# EVK-NORA-W4_SCHEM_0001_Power.net
KiCad netlist of a schematic drawn in Altium Designer
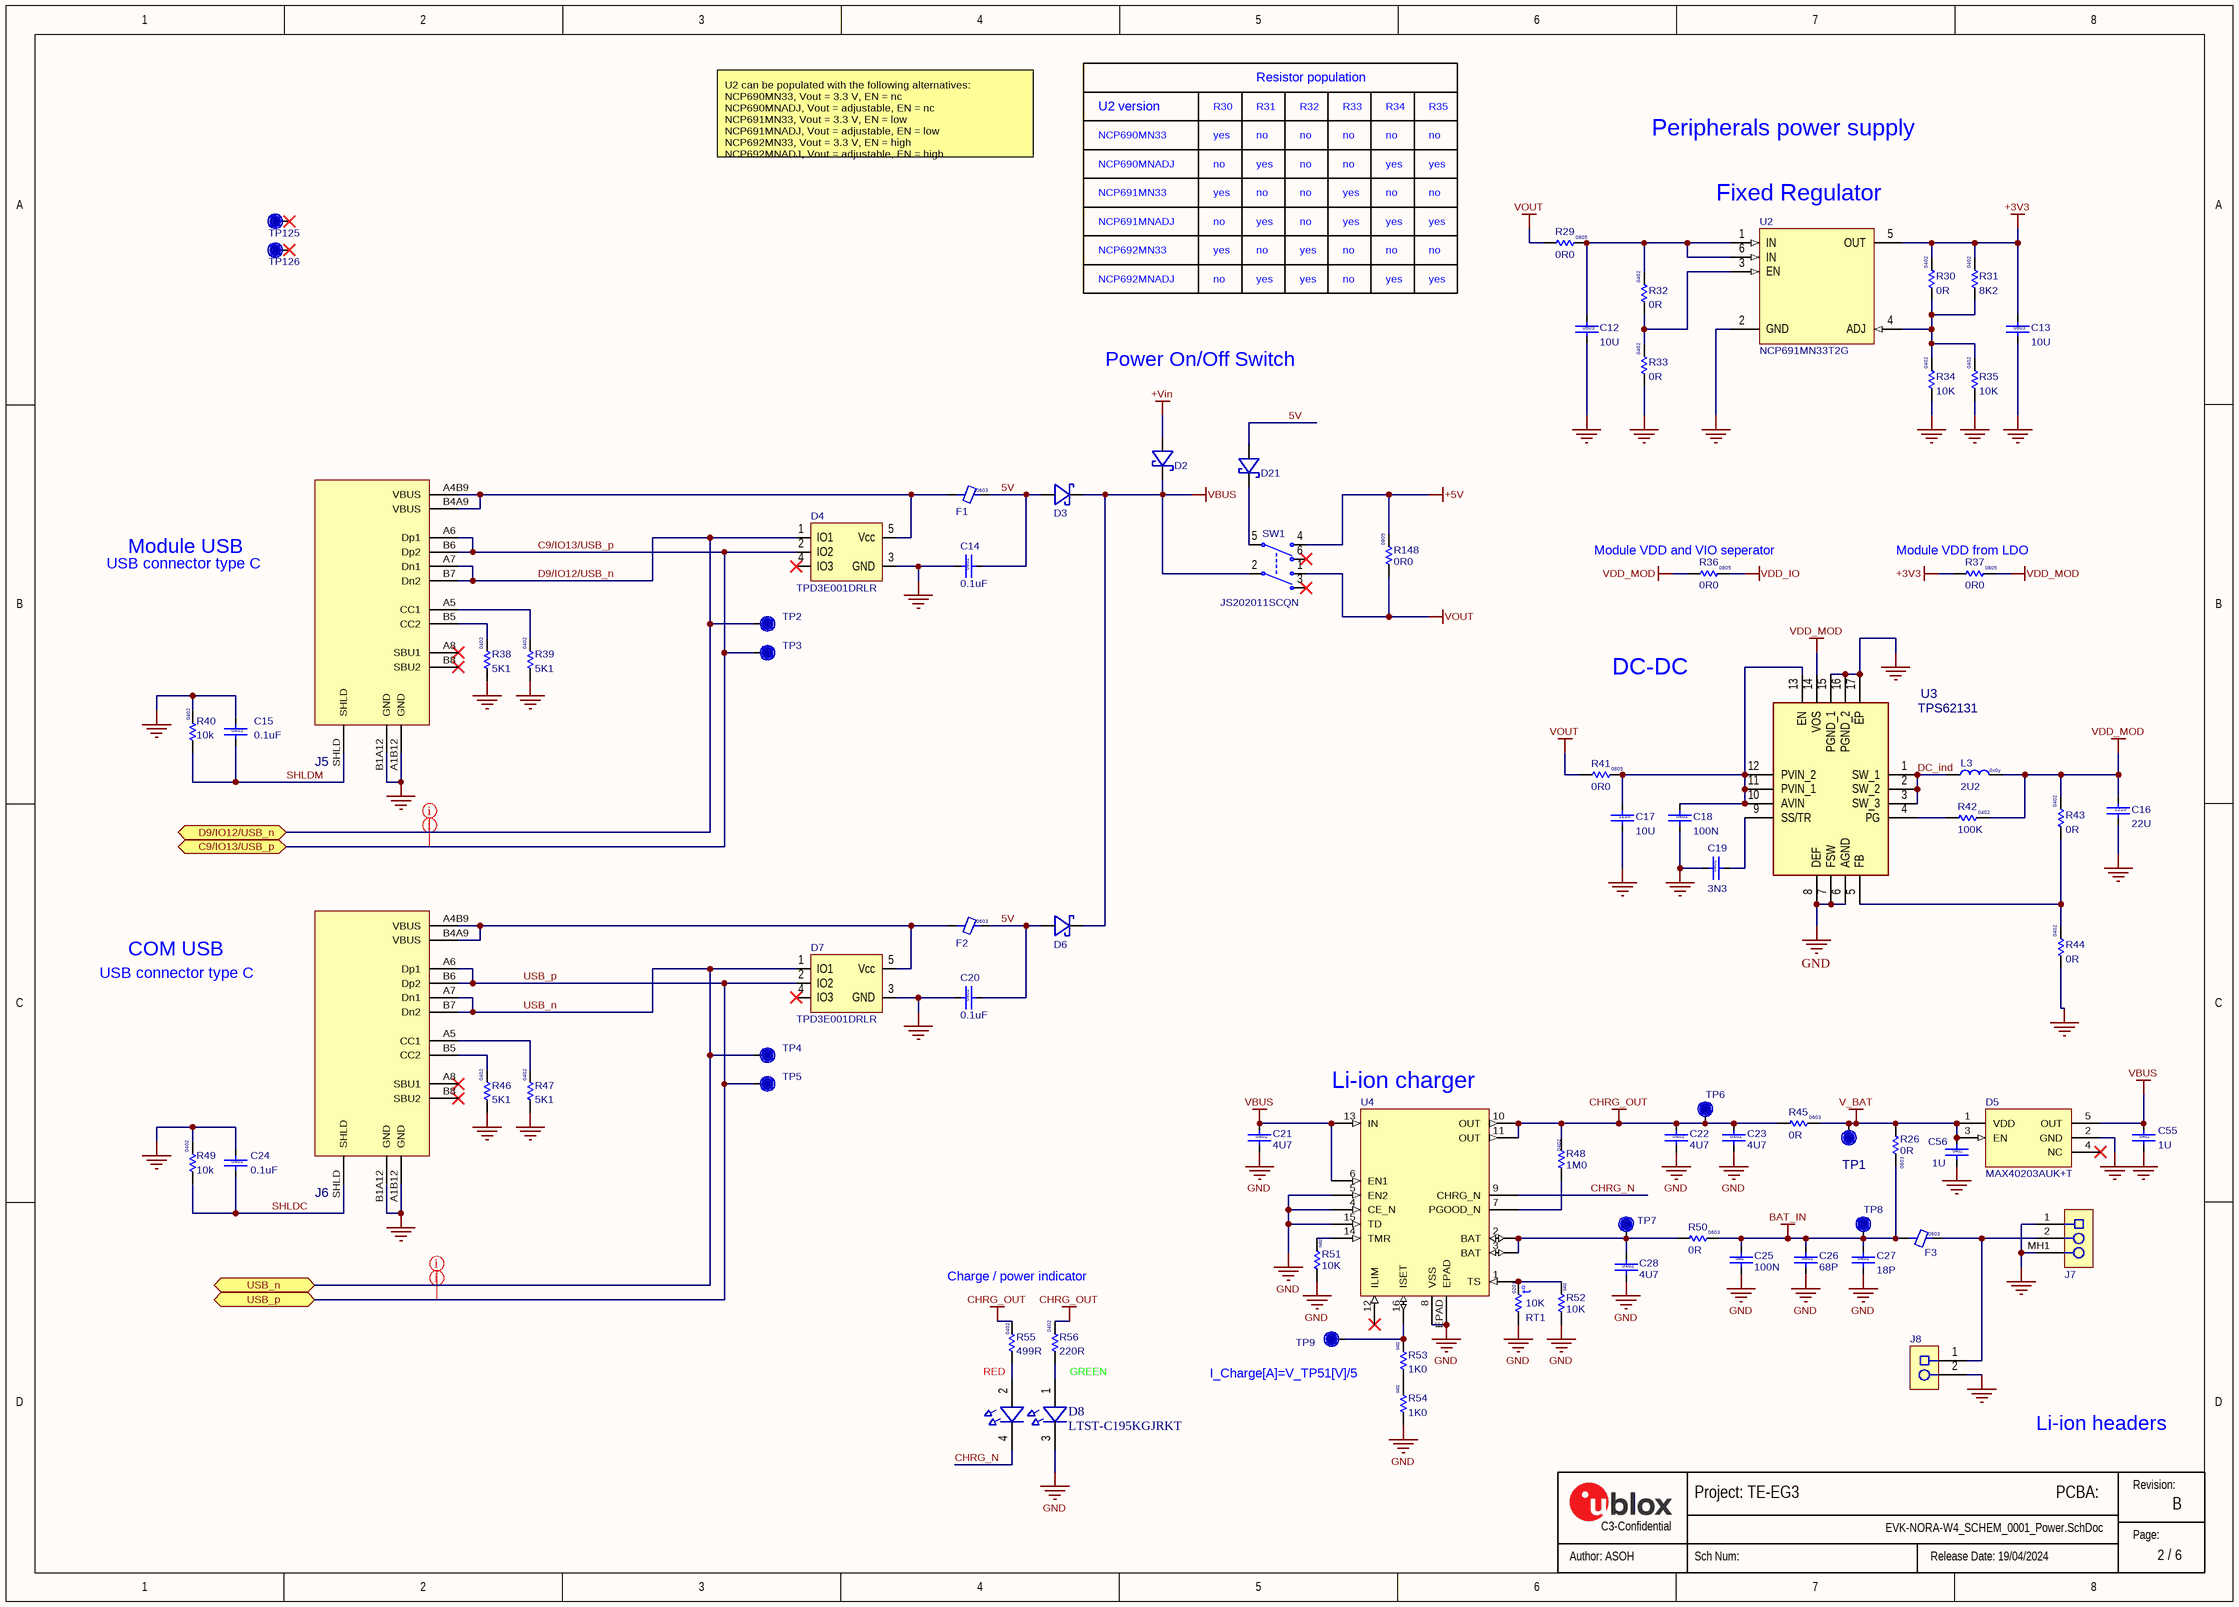
[diagram p0: EVK-NORA-W4_SCHEM_0001_Power.SchDoc]

(export (version "E")
  (design (tool "Eeschema 10.0.6"))
  (components
    (comp (ref "C12")
      (value "10U")
      (footprint "CAP_0603_1750Lx950Wx850H_600x1000Pad_900G_FLX")
      (description "CAP CER X7R 0603 10U 20% 10V")
      (fields
        (field (name "SIZE") "0603")
        (field (name "PART NUMBER") "UBXH01-0000310")
        (field (name "TOLERANCE") "20%")
        (field (name "EDITOR") "michael.hein")
        (field (name "RELEASED BY") "martin.grasse")
      )
      (libsource (lib "UBX_Parts_DB_Lib") (part "Cap Chip"))
    )
    (comp (ref "C13")
      (value "10U")
      (footprint "CAP_0603_1750Lx950Wx850H_600x1000Pad_900G_FLX")
      (description "CAP CER X7R 0603 10U 20% 10V")
      (fields
        (field (name "SIZE") "0603")
        (field (name "PART NUMBER") "UBXH01-0000310")
        (field (name "TOLERANCE") "20%")
        (field (name "EDITOR") "michael.hein")
        (field (name "RELEASED BY") "martin.grasse")
      )
      (libsource (lib "UBX_Parts_DB_Lib") (part "Cap Chip"))
    )
    (comp (ref "C14")
      (value "0.1uF")
      (footprint "Cap 0402 HD")
      (description "Cap, Ceramic 0.1uF 10V 10% X5R 0402")
      (fields
        (field (name "SIZE") "0402")
        (field (name "PART NUMBER") "120-00016")
        (field (name "MANUFACTURER") "Murata Electronics North America")
      )
      (libsource (lib "Arena_Parts_DB_Lib") (part "Cap Chip"))
    )
    (comp (ref "C15")
      (value "0.1uF")
      (footprint "Cap 0402 HD")
      (description "Cap, Ceramic 0.1uF 10V 10% X5R 0402")
      (fields
        (field (name "SIZE") "0402")
        (field (name "PART NUMBER") "120-00016")
        (field (name "MANUFACTURER") "Murata Electronics North America")
      )
      (libsource (lib "Arena_Parts_DB_Lib") (part "Cap Chip"))
    )
    (comp (ref "C16")
      (value "22U")
      (footprint "CAP_1210_3400Lx2700Wx1350H_900x2700Pad_1900G_FLX")
      (description "CAP CER X5R 1210 22U 10% 25V")
      (fields
        (field (name "SIZE") "1210")
        (field (name "PART NUMBER") "UBXH01-3001005")
        (field (name "TOLERANCE") "10%")
        (field (name "EDITOR") "roland.rust")
        (field (name "RELEASED BY") "roland.rust")
      )
      (libsource (lib "UBX_Parts_DB_Lib") (part "Cap Chip"))
    )
    (comp (ref "C17")
      (value "10U")
      (footprint "CAP_1210_3400Lx2700Wx1350H_900x2700Pad_1900G_FLX")
      (description "CAP CER X5R 1210 10U 10% 25V")
      (fields
        (field (name "SIZE") "1210")
        (field (name "PART NUMBER") "UBXH01-3001004")
        (field (name "TOLERANCE") "10%")
        (field (name "EDITOR") "andreas.thiel")
        (field (name "RELEASED BY") "johann.furrer")
      )
      (libsource (lib "UBX_Parts_DB_Lib") (part "Cap Chip"))
    )
    (comp (ref "C18")
      (value "100N")
      (footprint "Cap_0402_1100Lx600Wx600H_600x600Pad_350G_FLX")
      (description "CAP CER X5R 0402 100N 10% 50V")
      (fields
        (field (name "SIZE") "0402")
        (field (name "PART NUMBER") "UBXH01-0000204")
        (field (name "TOLERANCE") "10%")
        (field (name "EDITOR") "matej.budin")
        (field (name "RELEASED BY") "erian.bezhani")
      )
      (libsource (lib "UBX_Parts_DB_Lib") (part "Cap Chip"))
    )
    (comp (ref "C19")
      (value "3N3")
      (footprint "Cap_0402_1100Lx600Wx600H_600x600Pad_350G_FLX")
      (description "CAP CER X7R 0402 3N3 10% 16V")
      (fields
        (field (name "SIZE") "0402")
        (field (name "PART NUMBER") "UBXH01-0023019")
        (field (name "TOLERANCE") "10%")
        (field (name "EDITOR") "dario.antonaz")
        (field (name "RELEASED BY") "pierpaolo.arban")
      )
      (libsource (lib "UBX_Parts_DB_Lib") (part "Cap Chip"))
    )
    (comp (ref "C20")
      (value "0.1uF")
      (footprint "Cap 0402 HD")
      (description "Cap, Ceramic 0.1uF 10V 10% X5R 0402")
      (fields
        (field (name "SIZE") "0402")
        (field (name "PART NUMBER") "120-00016")
        (field (name "MANUFACTURER") "Murata Electronics North America")
      )
      (libsource (lib "Arena_Parts_DB_Lib") (part "Cap Chip"))
    )
    (comp (ref "C21")
      (value "4U7")
      (footprint "Cap 0402 HD")
      (description "CAP CER X5R 0402 4U7 20% 10V")
      (fields
        (field (name "SIZE") "0402")
        (field (name "PART NUMBER") "UBXH01-0000243")
        (field (name "TOLERANCE") "20%")
        (field (name "EDITOR") "martin.pilik")
        (field (name "RELEASED BY") "fabrice.bret-dibat")
      )
      (libsource (lib "UBX_Parts_DB_Lib") (part "Cap Chip"))
    )
    (comp (ref "C22")
      (value "4U7")
      (footprint "Cap 0402 HD")
      (description "CAP CER X5R 0402 4U7 20% 10V")
      (fields
        (field (name "SIZE") "0402")
        (field (name "PART NUMBER") "UBXH01-0000243")
        (field (name "TOLERANCE") "20%")
        (field (name "EDITOR") "martin.pilik")
        (field (name "RELEASED BY") "fabrice.bret-dibat")
      )
      (libsource (lib "UBX_Parts_DB_Lib") (part "Cap Chip"))
    )
    (comp (ref "C23")
      (value "4U7")
      (footprint "Cap 0402 HD")
      (description "CAP CER X5R 0402 4U7 20% 10V")
      (fields
        (field (name "SIZE") "0402")
        (field (name "PART NUMBER") "UBXH01-0000243")
        (field (name "TOLERANCE") "20%")
        (field (name "EDITOR") "martin.pilik")
        (field (name "RELEASED BY") "fabrice.bret-dibat")
      )
      (libsource (lib "UBX_Parts_DB_Lib") (part "Cap Chip"))
    )
    (comp (ref "C24")
      (value "0.1uF")
      (footprint "Cap 0402 HD")
      (description "Cap, Ceramic 0.1uF 10V 10% X5R 0402")
      (fields
        (field (name "SIZE") "0402")
        (field (name "PART NUMBER") "120-00016")
        (field (name "MANUFACTURER") "Murata Electronics North America")
      )
      (libsource (lib "Arena_Parts_DB_Lib") (part "Cap Chip"))
    )
    (comp (ref "C25")
      (value "100N")
      (footprint "Cap 0402 HD")
      (description "CAP CER X5R 0402 100N 10% 10V")
      (fields
        (field (name "SIZE") "0402")
        (field (name "PART NUMBER") "UBXH01-2021002")
        (field (name "TOLERANCE") "10%")
        (field (name "EDITOR") "roland.rust")
        (field (name "RELEASED BY") "roland.rust")
      )
      (libsource (lib "UBX_Parts_DB_Lib") (part "Cap Chip"))
    )
    (comp (ref "C26")
      (value "68P")
      (footprint "Cap 0402 HD")
      (description "CAP CER C0G 0402 68P 5% 25V")
      (fields
        (field (name "SIZE") "0402")
        (field (name "PART NUMBER") "UBXH01-0004024")
        (field (name "TOLERANCE") "5%")
        (field (name "EDITOR") "martin.frauchiger")
        (field (name "RELEASED BY") "martin.frauchiger")
      )
      (libsource (lib "UBX_Parts_DB_Lib") (part "Cap Chip"))
    )
    (comp (ref "C27")
      (value "18P")
      (footprint "Cap_0402_1100Lx600Wx600H_600x600Pad_350G_FLX")
      (description "CAP CER C0G 0402 18P 5% 25V")
      (fields
        (field (name "SIZE") "0402")
        (field (name "PART NUMBER") "UBXH01-0004017")
        (field (name "TOLERANCE") "5%")
        (field (name "EDITOR") "doris.zahnd")
        (field (name "RELEASED BY") "daniel.hurni")
      )
      (libsource (lib "UBX_Parts_DB_Lib") (part "Cap Chip"))
    )
    (comp (ref "C28")
      (value "4U7")
      (footprint "Cap 0402 HD")
      (description "CAP CER X5R 0402 4U7 20% 10V")
      (fields
        (field (name "SIZE") "0402")
        (field (name "PART NUMBER") "UBXH01-0000243")
        (field (name "TOLERANCE") "20%")
        (field (name "EDITOR") "martin.pilik")
        (field (name "RELEASED BY") "fabrice.bret-dibat")
      )
      (libsource (lib "UBX_Parts_DB_Lib") (part "Cap Chip"))
    )
    (comp (ref "C55")
      (value "1U")
      (footprint "Cap 0402 HD")
      (description "CAP CER X5R 0402 1U 10% 10V")
      (fields
        (field (name "SIZE") "0402")
        (field (name "PART NUMBER") "UBXH01-0000248")
        (field (name "TOLERANCE") "10%")
        (field (name "EDITOR") "michael.hein")
        (field (name "RELEASED BY") "igor.shevchenko")
      )
      (libsource (lib "UBX_Parts_DB_Lib") (part "Cap Chip"))
    )
    (comp (ref "C56")
      (value "1U")
      (footprint "Cap 0402 HD")
      (description "CAP CER X5R 0402 1U 10% 10V")
      (fields
        (field (name "SIZE") "0402")
        (field (name "PART NUMBER") "UBXH01-0000248")
        (field (name "TOLERANCE") "10%")
        (field (name "EDITOR") "michael.hein")
        (field (name "RELEASED BY") "igor.shevchenko")
      )
      (libsource (lib "UBX_Parts_DB_Lib") (part "Cap Chip"))
    )
    (comp (ref "D2")
      (value "110-00005")
      (footprint "SOD-123F_U")
      (description "Diode, Schottky, 20V 1A SOD-123F, 340mV Vf @ 1A\nMBR120VLSFT3G")
      (fields (field (name "VOLTAGE") "20V"))
      (libsource (lib "Arena_Parts_DB_Lib") (part "Diode_Schottky"))
    )
    (comp (ref "D3")
      (value "110-00005")
      (footprint "SOD-123F_U")
      (description "Diode, Schottky, 20V 1A SOD-123F, 340mV Vf @ 1A\nMBR120VLSFT3G")
      (fields (field (name "VOLTAGE") "20V"))
      (libsource (lib "Arena_Parts_DB_Lib") (part "Diode_Schottky"))
    )
    (comp (ref "D4")
      (value "110-00018")
      (footprint "SOT-553")
      (description "LOW-CAPACITANCE 3-CHANNEL ESD-PROTECTION ARRAY")
      (fields
        (field (name "MANUFACTURER P/N") "TPD3E001DRLR")
        (field (name "MANUFACTURER") "Texas Instruments")
        (field (name "VOLTAGE") "5V")
      )
      (libsource (lib "Arena_Parts_DB_Lib") (part "TPD3E001"))
    )
    (comp (ref "D5")
      (value "UBXH12-0000539")
      (footprint "SOT-23-5_2")
      (description "IDEAL DIODE OR CONTROLLER SOURCE SELECTOR SWITCH P-CHANNEL 1:1 SOT-23-5 5.5V 1A")
      (fields
        (field (name "VOLTAGE") "5.5V")
        (field (name "MANUFACTURER PART NUMBER 1") "MAX40203AUK+T")
        (field (name "MANUFACTURER") "Maxim")
        (field (name "EDITOR") "eric.moog")
      )
      (libsource (lib "UBX_Parts_DB_Lib") (part "MAX40203AUK"))
    )
    (comp (ref "D6")
      (value "110-00005")
      (footprint "SOD-123F_U")
      (description "Diode, Schottky, 20V 1A SOD-123F, 340mV Vf @ 1A\nMBR120VLSFT3G")
      (fields (field (name "VOLTAGE") "20V"))
      (libsource (lib "Arena_Parts_DB_Lib") (part "Diode_Schottky"))
    )
    (comp (ref "D7")
      (value "110-00018")
      (footprint "SOT-553")
      (description "LOW-CAPACITANCE 3-CHANNEL ESD-PROTECTION ARRAY")
      (fields
        (field (name "MANUFACTURER P/N") "TPD3E001DRLR")
        (field (name "MANUFACTURER") "Texas Instruments")
        (field (name "VOLTAGE") "5V")
      )
      (libsource (lib "Arena_Parts_DB_Lib") (part "TPD3E001"))
    )
    (comp (ref "D8")
      (value "LTST-C195KGJRKT")
      (footprint "SamacSys:LTSTC195KGJRKT")
      (description "LED")
      (fields (field (name "MOUSER PART NUMBER") "859-LTST-C195KGJRKT"))
      (libsource (lib "SamacSys") (part "LTST-C195KGJRKT"))
    )
    (comp (ref "D21")
      (value "110-00005")
      (footprint "SOD-123F_U")
      (description "Diode, Schottky, 20V 1A SOD-123F, 340mV Vf @ 1A\nMBR120VLSFT3G")
      (fields (field (name "VOLTAGE") "20V"))
      (libsource (lib "Arena_Parts_DB_Lib") (part "Diode_Schottky"))
    )
    (comp (ref "F1")
      (value "UBXH08-0000001")
      (footprint "IND_0603_1750Lx950Wx1050H_600x800Pad_800G_FLX")
      (description "FERRITE BEAD 0603 600 OHM AT 100MHZ 600OHM 500mA")
      (fields
        (field (name "SIZE") "0603")
        (field (name "MANUFACTURER") "TDK Corporation")
        (field (name "EDITOR") "daniel.hurni")
        (field (name "RELEASED BY") "martin.frauchiger")
      )
      (libsource (lib "UBX_Parts_DB_Lib") (part "FB sm"))
    )
    (comp (ref "F2")
      (value "UBXH08-0000001")
      (footprint "IND_0603_1750Lx950Wx1050H_600x800Pad_800G_FLX")
      (description "FERRITE BEAD 0603 600 OHM AT 100MHZ 600OHM 500mA")
      (fields
        (field (name "SIZE") "0603")
        (field (name "MANUFACTURER") "TDK Corporation")
        (field (name "EDITOR") "daniel.hurni")
        (field (name "RELEASED BY") "martin.frauchiger")
      )
      (libsource (lib "UBX_Parts_DB_Lib") (part "FB sm"))
    )
    (comp (ref "F3")
      (value "UBXH08-0000001")
      (footprint "IND_0603_1750Lx950Wx1050H_600x800Pad_800G_FLX")
      (description "FERRITE BEAD 0603 600 OHM AT 100MHZ 600OHM 500mA")
      (fields
        (field (name "SIZE") "0603")
        (field (name "MANUFACTURER") "TDK Corporation")
        (field (name "EDITOR") "daniel.hurni")
        (field (name "RELEASED BY") "martin.frauchiger")
      )
      (libsource (lib "UBX_Parts_DB_Lib") (part "FB sm"))
    )
    (comp (ref "J5")
      (value "USB4105-GF-A")
      (footprint "USB4105-GF-A")
      (description "CONN RCP USB2.0 TYP C 24P SMD RA 20V 6.25A")
      (fields
        (field (name "PART NUMBER") "UBXH04-0000785")
        (field (name "VOLTAGE") "<20V DC")
        (field (name "EDITOR") "eric.moog")
      )
      (libsource (lib "UBX_Parts_DB_Lib") (part "USB4105-GF-A"))
    )
    (comp (ref "J6")
      (value "USB4105-GF-A")
      (footprint "USB4105-GF-A")
      (description "CONN RCP USB2.0 TYP C 24P SMD RA 20V 6.25A")
      (fields
        (field (name "PART NUMBER") "UBXH04-0000785")
        (field (name "VOLTAGE") "<20V DC")
        (field (name "EDITOR") "eric.moog")
      )
      (libsource (lib "UBX_Parts_DB_Lib") (part "USB4105-GF-A"))
    )
    (comp (ref "J7")
      (value "UBXH04-0000791")
      (footprint "B2B-PH-SM4-TB")
      (description "CONN 1-ROW SMT 2.0MM GRID 2-PIN VERT 100V 2A")
      (fields
        (field (name "VOLTAGE") "None")
        (field (name "MANUFACTURER") "JST")
        (field (name "EDITOR") "eric.moog")
      )
      (libsource (lib "UBX_Parts_DB_Lib") (part "CON-2Pin_1Row_W-MH"))
    )
    (comp (ref "J8")
      (value "UBXH04-0000026")
      (footprint "HDR-0.1P-2PIN-TH")
      (description "1-ROW TH-PCB SOCKETS 100MIL GRID 2-PIN 0.64MM SQUARE POLARIZE")
      (fields
        (field (name "MANUFACTURER") "HARWiN")
        (field (name "EDITOR") "roland.rust")
        (field (name "RELEASED BY") "alvaro.nussbaum")
      )
      (libsource (lib "UBX_Parts_DB_Lib") (part "CON-2Pin_1Row"))
    )
    (comp (ref "L3")
      (value "2U2")
      (footprint "IND_0603_1800Lx1000Wx1000H_600x1000Pad_650G_FLX")
      (description "IND TAIYOYUDEN MCHK1608T 2U2 20% 1.5A")
      (fields
        (field (name "SIZE") "0x0y")
        (field (name "PART NUMBER") "UBXH09-0000330")
        (field (name "TOLERANCE") "20%")
        (field (name "EDITOR") "martin.grasse")
        (field (name "RELEASED BY") "igor.shevchenko")
      )
      (libsource (lib "UBX_Parts_DB_Lib") (part "Ind sm"))
    )
    (comp (ref "R26")
      (value "0R")
      (footprint "RES_0603_1700Lx950Wx600H_600x1000Pad_800G_FLX")
      (description "RES THICK FILM CHIP 0603 0R 0 100mW")
      (fields
        (field (name "SIZE") "0603")
        (field (name "PART NUMBER") "UBXH18-0003001")
        (field (name "TOLERANCE") "0")
        (field (name "EDITOR") "martin.frauchiger")
        (field (name "RELEASED BY") "martin.frauchiger")
      )
      (libsource (lib "UBX_Parts_DB_Lib") (part "Res sm"))
    )
    (comp (ref "R29")
      (value "0R0")
      (footprint "RES 0805_2150Lx1400Wx650H_800x1300Pad_1000G_FLX")
      (description "RES THICK FILM CHIP 0805 0R015 1% 330mW")
      (fields
        (field (name "SIZE") "0805")
        (field (name "TOLERANCE") "1%")
        (field (name "MANUFACTURER") "KOA Speer Electronics, Inc.")
        (field (name "EDITOR") "roland.rust")
        (field (name "RELEASED BY") "frank.felbier")
      )
      (libsource (lib "UBX_Parts_DB_Lib") (part "Res sm"))
    )
    (comp (ref "R30")
      (value "0R")
      (footprint "RES 0402 HD")
      (description "RES THICK FILM CHIP 0402 0R 0 100mW")
      (fields
        (field (name "SIZE") "0402")
        (field (name "PART NUMBER") "UBXH18-0003002")
        (field (name "TOLERANCE") "0")
        (field (name "EDITOR") "charlotte.biber")
        (field (name "RELEASED BY") "peter.mueller")
      )
      (libsource (lib "UBX_Parts_DB_Lib") (part "Res sm"))
    )
    (comp (ref "R31")
      (value "8K2")
      (footprint "RES_0402_1100Lx600Wx400H_500x600Pad_400G_FLX")
      (description "RES THICK FILM CHIP 0402 8K2 1% 63mW")
      (fields
        (field (name "SIZE") "0402")
        (field (name "PART NUMBER") "UBXH18-0000138")
        (field (name "TOLERANCE") "1%")
        (field (name "EDITOR") "matej.budin")
        (field (name "RELEASED BY") "pasquale.scorca")
      )
      (libsource (lib "UBX_Parts_DB_Lib") (part "Res sm"))
    )
    (comp (ref "R32")
      (value "0R")
      (footprint "RES 0402 HD")
      (description "RES THICK FILM CHIP 0402 0R 0 100mW")
      (fields
        (field (name "SIZE") "0402")
        (field (name "PART NUMBER") "UBXH18-0003002")
        (field (name "TOLERANCE") "0")
        (field (name "EDITOR") "charlotte.biber")
        (field (name "RELEASED BY") "peter.mueller")
      )
      (libsource (lib "UBX_Parts_DB_Lib") (part "Res sm"))
    )
    (comp (ref "R33")
      (value "0R")
      (footprint "RES 0402 HD")
      (description "RES THICK FILM CHIP 0402 0R 0 100mW")
      (fields
        (field (name "SIZE") "0402")
        (field (name "PART NUMBER") "UBXH18-0003002")
        (field (name "TOLERANCE") "0")
        (field (name "EDITOR") "charlotte.biber")
        (field (name "RELEASED BY") "peter.mueller")
      )
      (libsource (lib "UBX_Parts_DB_Lib") (part "Res sm"))
    )
    (comp (ref "R34")
      (value "10K")
      (footprint "RES 0402 HD")
      (description "RES THICK FILM CHIP 0402 10K 1% 63mW")
      (fields
        (field (name "SIZE") "0402")
        (field (name "PART NUMBER") "UBXH18-0000065")
        (field (name "TOLERANCE") "1%")
        (field (name "EDITOR") "erian.bezhani")
        (field (name "RELEASED BY") "massimo.vlacci")
      )
      (libsource (lib "UBX_Parts_DB_Lib") (part "Res sm"))
    )
    (comp (ref "R35")
      (value "10K")
      (footprint "RES 0402 HD")
      (description "RES THICK FILM CHIP 0402 10K 1% 63mW")
      (fields
        (field (name "SIZE") "0402")
        (field (name "PART NUMBER") "UBXH18-0000065")
        (field (name "TOLERANCE") "1%")
        (field (name "EDITOR") "erian.bezhani")
        (field (name "RELEASED BY") "massimo.vlacci")
      )
      (libsource (lib "UBX_Parts_DB_Lib") (part "Res sm"))
    )
    (comp (ref "R36")
      (value "0R0")
      (footprint "RES 0805_2150Lx1400Wx650H_800x1300Pad_1000G_FLX")
      (description "RES THICK FILM CHIP 0805 0R015 1% 330mW")
      (fields
        (field (name "SIZE") "0805")
        (field (name "TOLERANCE") "1%")
        (field (name "MANUFACTURER") "KOA Speer Electronics, Inc.")
        (field (name "EDITOR") "roland.rust")
        (field (name "RELEASED BY") "frank.felbier")
      )
      (libsource (lib "UBX_Parts_DB_Lib") (part "Res sm"))
    )
    (comp (ref "R37")
      (value "0R0")
      (footprint "RES 0805_2150Lx1400Wx650H_800x1300Pad_1000G_FLX")
      (description "RES THICK FILM CHIP 0805 0R015 1% 330mW")
      (fields
        (field (name "SIZE") "0805")
        (field (name "TOLERANCE") "1%")
        (field (name "MANUFACTURER") "KOA Speer Electronics, Inc.")
        (field (name "EDITOR") "roland.rust")
        (field (name "RELEASED BY") "frank.felbier")
      )
      (libsource (lib "UBX_Parts_DB_Lib") (part "Res sm"))
    )
    (comp (ref "R38")
      (value "5K1")
      (footprint "RES 0402 HD")
      (description "RES THICK FILM CHIP 0402 5K1 5% 100mW")
      (fields
        (field (name "SIZE") "0402")
        (field (name "PART NUMBER") "UBXH18-0008066")
        (field (name "TOLERANCE") "5%")
        (field (name "EDITOR") "alvaro.nussbaum")
        (field (name "RELEASED BY") "roland.rust")
      )
      (libsource (lib "UBX_Parts_DB_Lib") (part "Res sm"))
    )
    (comp (ref "R39")
      (value "5K1")
      (footprint "RES 0402 HD")
      (description "RES THICK FILM CHIP 0402 5K1 5% 100mW")
      (fields
        (field (name "SIZE") "0402")
        (field (name "PART NUMBER") "UBXH18-0008066")
        (field (name "TOLERANCE") "5%")
        (field (name "EDITOR") "alvaro.nussbaum")
        (field (name "RELEASED BY") "roland.rust")
      )
      (libsource (lib "UBX_Parts_DB_Lib") (part "Res sm"))
    )
    (comp (ref "R40")
      (value "10k")
      (footprint "RES 0402 HD")
      (description "Resistor 10k ohm 1% 1/16W, 0402")
      (fields
        (field (name "SIZE") "0402")
        (field (name "PART NUMBER") "180-00024")
        (field (name "POWER") "1/16W")
      )
      (libsource (lib "Arena_Parts_DB_Lib") (part "Res sm"))
    )
    (comp (ref "R41")
      (value "0R0")
      (footprint "RES 0805_2150Lx1400Wx650H_800x1300Pad_1000G_FLX")
      (description "RES THICK FILM CHIP 0805 0R015 1% 330mW")
      (fields
        (field (name "SIZE") "0805")
        (field (name "TOLERANCE") "1%")
        (field (name "MANUFACTURER") "KOA Speer Electronics, Inc.")
        (field (name "EDITOR") "roland.rust")
        (field (name "RELEASED BY") "frank.felbier")
      )
      (libsource (lib "UBX_Parts_DB_Lib") (part "Res sm"))
    )
    (comp (ref "R42")
      (value "100K")
      (footprint "RES 0402 HD")
      (description "RES THICK FILM CHIP 0402 100K 1% 63mW")
      (fields
        (field (name "SIZE") "0402")
        (field (name "PART NUMBER") "UBXH18-0000005")
        (field (name "TOLERANCE") "1%")
        (field (name "EDITOR") "dario.antonaz")
        (field (name "RELEASED BY") "sandro.sestan")
      )
      (libsource (lib "UBX_Parts_DB_Lib") (part "Res sm"))
    )
    (comp (ref "R43")
      (value "0R")
      (footprint "RES 0402 HD")
      (description "RES THICK FILM CHIP 0402 0R 0 100mW")
      (fields
        (field (name "SIZE") "0402")
        (field (name "PART NUMBER") "UBXH18-0003002")
        (field (name "TOLERANCE") "0")
        (field (name "EDITOR") "charlotte.biber")
        (field (name "RELEASED BY") "peter.mueller")
      )
      (libsource (lib "UBX_Parts_DB_Lib") (part "Res sm"))
    )
    (comp (ref "R44")
      (value "0R")
      (footprint "RES 0402 HD")
      (description "RES THICK FILM CHIP 0402 0R 0 100mW")
      (fields
        (field (name "SIZE") "0402")
        (field (name "PART NUMBER") "UBXH18-0003002")
        (field (name "TOLERANCE") "0")
        (field (name "EDITOR") "charlotte.biber")
        (field (name "RELEASED BY") "peter.mueller")
      )
      (libsource (lib "UBX_Parts_DB_Lib") (part "Res sm"))
    )
    (comp (ref "R45")
      (value "0R")
      (footprint "RES_0603_1700Lx950Wx600H_600x1000Pad_800G_FLX")
      (description "RES THICK FILM CHIP 0603 0R 0 100mW")
      (fields
        (field (name "SIZE") "0603")
        (field (name "PART NUMBER") "UBXH18-0003001")
        (field (name "TOLERANCE") "0")
        (field (name "EDITOR") "martin.frauchiger")
        (field (name "RELEASED BY") "martin.frauchiger")
      )
      (libsource (lib "UBX_Parts_DB_Lib") (part "Res sm"))
    )
    (comp (ref "R46")
      (value "5K1")
      (footprint "RES 0402 HD")
      (description "RES THICK FILM CHIP 0402 5K1 5% 100mW")
      (fields
        (field (name "SIZE") "0402")
        (field (name "PART NUMBER") "UBXH18-0008066")
        (field (name "TOLERANCE") "5%")
        (field (name "EDITOR") "alvaro.nussbaum")
        (field (name "RELEASED BY") "roland.rust")
      )
      (libsource (lib "UBX_Parts_DB_Lib") (part "Res sm"))
    )
    (comp (ref "R47")
      (value "5K1")
      (footprint "RES 0402 HD")
      (description "RES THICK FILM CHIP 0402 5K1 5% 100mW")
      (fields
        (field (name "SIZE") "0402")
        (field (name "PART NUMBER") "UBXH18-0008066")
        (field (name "TOLERANCE") "5%")
        (field (name "EDITOR") "alvaro.nussbaum")
        (field (name "RELEASED BY") "roland.rust")
      )
      (libsource (lib "UBX_Parts_DB_Lib") (part "Res sm"))
    )
    (comp (ref "R48")
      (value "1M0")
      (footprint "RES 0402 HD")
      (description "RES THICK FILM CHIP 0402 1M0 5% 63mW")
      (fields
        (field (name "SIZE") "0402")
        (field (name "PART NUMBER") "UBXH18-0008121")
        (field (name "TOLERANCE") "5%")
        (field (name "EDITOR") "daniel.hurni")
        (field (name "RELEASED BY") "doris.zahnd")
      )
      (libsource (lib "UBX_Parts_DB_Lib") (part "Res sm"))
    )
    (comp (ref "R49")
      (value "10k")
      (footprint "RES 0402 HD")
      (description "Resistor 10k ohm 1% 1/16W, 0402")
      (fields
        (field (name "SIZE") "0402")
        (field (name "PART NUMBER") "180-00024")
        (field (name "POWER") "1/16W")
      )
      (libsource (lib "Arena_Parts_DB_Lib") (part "Res sm"))
    )
    (comp (ref "R50")
      (value "0R")
      (footprint "RES_0603_1700Lx950Wx600H_600x1000Pad_800G_FLX")
      (description "RES THICK FILM CHIP 0603 0R 0 100mW")
      (fields
        (field (name "SIZE") "0603")
        (field (name "PART NUMBER") "UBXH18-0003001")
        (field (name "TOLERANCE") "0")
        (field (name "EDITOR") "martin.frauchiger")
        (field (name "RELEASED BY") "martin.frauchiger")
      )
      (libsource (lib "UBX_Parts_DB_Lib") (part "Res sm"))
    )
    (comp (ref "R51")
      (value "10K")
      (footprint "RES 0402 HD")
      (description "RES THICK FILM CHIP 0402 10K 1% 63mW")
      (fields
        (field (name "SIZE") "0402")
        (field (name "PART NUMBER") "UBXH18-0000065")
        (field (name "TOLERANCE") "1%")
        (field (name "EDITOR") "erian.bezhani")
        (field (name "RELEASED BY") "massimo.vlacci")
      )
      (libsource (lib "UBX_Parts_DB_Lib") (part "Res sm"))
    )
    (comp (ref "R52")
      (value "10K")
      (footprint "RES 0402 HD")
      (description "RES THICK FILM CHIP 0402 10K 1% 63mW")
      (fields
        (field (name "SIZE") "0402")
        (field (name "PART NUMBER") "UBXH18-0000065")
        (field (name "TOLERANCE") "1%")
        (field (name "EDITOR") "erian.bezhani")
        (field (name "RELEASED BY") "massimo.vlacci")
      )
      (libsource (lib "UBX_Parts_DB_Lib") (part "Res sm"))
    )
    (comp (ref "R53")
      (value "1K0")
      (footprint "RES 0402 HD")
      (description "RES THICK FILM CHIP 0402 1K0 5% 100mW")
      (fields
        (field (name "SIZE") "0402")
        (field (name "PART NUMBER") "UBXH18-0008049")
        (field (name "TOLERANCE") "5%")
        (field (name "EDITOR") "roland.rust")
        (field (name "RELEASED BY") "roland.rust")
      )
      (libsource (lib "UBX_Parts_DB_Lib") (part "Res sm"))
    )
    (comp (ref "R54")
      (value "1K0")
      (footprint "RES 0402 HD")
      (description "RES THICK FILM CHIP 0402 1K0 5% 100mW")
      (fields
        (field (name "SIZE") "0402")
        (field (name "PART NUMBER") "UBXH18-0008049")
        (field (name "TOLERANCE") "5%")
        (field (name "EDITOR") "roland.rust")
        (field (name "RELEASED BY") "roland.rust")
      )
      (libsource (lib "UBX_Parts_DB_Lib") (part "Res sm"))
    )
    (comp (ref "R55")
      (value "499R")
      (footprint "RES 0402 HD")
      (description "RES THICK FILM CHIP 0402 499R 1% 100mW")
      (fields
        (field (name "SIZE") "0402")
        (field (name "PART NUMBER") "UBXH18-0000269")
        (field (name "TOLERANCE") "1%")
        (field (name "EDITOR") "pierpaolo.arban")
      )
      (libsource (lib "UBX_Parts_DB_Lib") (part "Res sm"))
    )
    (comp (ref "R56")
      (value "220R")
      (footprint "RES 0402 HD")
      (description "RES THICK FILM CHIP 0402 220R 5% 100mW")
      (fields
        (field (name "SIZE") "0402")
        (field (name "PART NUMBER") "UBXH18-0008033")
        (field (name "TOLERANCE") "5%")
        (field (name "EDITOR") "roland.rust")
        (field (name "RELEASED BY") "roland.rust")
      )
      (libsource (lib "UBX_Parts_DB_Lib") (part "Res sm"))
    )
    (comp (ref "R148")
      (value "0R0")
      (footprint "RES 0805_2150Lx1400Wx650H_800x1300Pad_1000G_FLX")
      (description "RES THICK FILM CHIP 0805 0R015 1% 330mW")
      (fields
        (field (name "SIZE") "0805")
        (field (name "TOLERANCE") "1%")
        (field (name "MANUFACTURER") "KOA Speer Electronics, Inc.")
        (field (name "EDITOR") "roland.rust")
        (field (name "RELEASED BY") "frank.felbier")
      )
      (libsource (lib "UBX_Parts_DB_Lib") (part "Res sm"))
    )
    (comp (ref "RT1")
      (value "10K")
      (footprint "RES 0201")
      (description "THERMISTOR NTC 0201 10K 5% 100mW")
      (fields
        (field (name "SIZE") "0201")
        (field (name "PART NUMBER") "UBXH18-0000573")
        (field (name "TOLERANCE") "5%")
        (field (name "EDITOR") "eric.moog")
      )
      (libsource (lib "UBX_Parts_DB_Lib") (part "Res Thermal"))
    )
    (comp (ref "SW1")
      (value "UBXH19-0000050")
      (footprint "SW_Slide_DPDT_JS202011SCQN")
      (description "2 WAY ON-ON SUB-MINIATURE SLIDE SWITCH SMD JS SERIES")
      (fields
        (field (name "MANUFACTURER P/N") "JS202011SCQN")
        (field (name "MANUFACTURER") "C&K Components")
        (field (name "EDITOR") "andre.pick")
        (field (name "RELEASED BY") "martin.pilik")
      )
      (libsource (lib "UBX_Parts_DB_Lib") (part "SW_DPDT_JS2020"))
    )
    (comp (ref "TP1")
      (value "TP")
      (footprint "TP10R")
      (description "Testpoint, Round 1.0mm Dia")
      (fields
        (field (name "PART NUMBER") "TP10R")
        (field (name "ADDED BY") "Jeremy D")
        (field (name "CHECKED BY") "Paul B")
      )
      (libsource (lib "LEGACY_Rigado_AltiumLib") (part "TP_R"))
    )
    (comp (ref "TP2")
      (value "TP")
      (footprint "TP10R")
      (description "Testpoint, Round 1.0mm Dia")
      (fields
        (field (name "PART NUMBER") "TP10R")
        (field (name "ADDED BY") "Jeremy D")
        (field (name "CHECKED BY") "Paul B")
      )
      (libsource (lib "LEGACY_Rigado_AltiumLib") (part "TP_R"))
    )
    (comp (ref "TP3")
      (value "TP")
      (footprint "TP10R")
      (description "Testpoint, Round 1.0mm Dia")
      (fields
        (field (name "PART NUMBER") "TP10R")
        (field (name "ADDED BY") "Jeremy D")
        (field (name "CHECKED BY") "Paul B")
      )
      (libsource (lib "LEGACY_Rigado_AltiumLib") (part "TP_R"))
    )
    (comp (ref "TP4")
      (value "TP")
      (footprint "TP10R")
      (description "Testpoint, Round 1.0mm Dia")
      (fields
        (field (name "PART NUMBER") "TP10R")
        (field (name "ADDED BY") "Jeremy D")
        (field (name "CHECKED BY") "Paul B")
      )
      (libsource (lib "LEGACY_Rigado_AltiumLib") (part "TP_R"))
    )
    (comp (ref "TP5")
      (value "TP")
      (footprint "TP10R")
      (description "Testpoint, Round 1.0mm Dia")
      (fields
        (field (name "PART NUMBER") "TP10R")
        (field (name "ADDED BY") "Jeremy D")
        (field (name "CHECKED BY") "Paul B")
      )
      (libsource (lib "LEGACY_Rigado_AltiumLib") (part "TP_R"))
    )
    (comp (ref "TP6")
      (value "TP")
      (footprint "TP10R")
      (description "Testpoint, Round 1.0mm Dia")
      (fields
        (field (name "PART NUMBER") "TP10R")
        (field (name "ADDED BY") "Jeremy D")
        (field (name "CHECKED BY") "Paul B")
      )
      (libsource (lib "LEGACY_Rigado_AltiumLib") (part "TP_R"))
    )
    (comp (ref "TP7")
      (value "TP")
      (footprint "TP10R")
      (description "Testpoint, Round 1.0mm Dia")
      (fields
        (field (name "PART NUMBER") "TP10R")
        (field (name "ADDED BY") "Jeremy D")
        (field (name "CHECKED BY") "Paul B")
      )
      (libsource (lib "LEGACY_Rigado_AltiumLib") (part "TP_R"))
    )
    (comp (ref "TP8")
      (value "TP")
      (footprint "TP10R")
      (description "Testpoint, Round 1.0mm Dia")
      (fields
        (field (name "PART NUMBER") "TP10R")
        (field (name "ADDED BY") "Jeremy D")
        (field (name "CHECKED BY") "Paul B")
      )
      (libsource (lib "LEGACY_Rigado_AltiumLib") (part "TP_R"))
    )
    (comp (ref "TP9")
      (value "TP")
      (footprint "TP10R")
      (description "Testpoint, Round 1.0mm Dia")
      (fields
        (field (name "PART NUMBER") "TP10R")
        (field (name "ADDED BY") "Jeremy D")
        (field (name "CHECKED BY") "Paul B")
      )
      (libsource (lib "LEGACY_Rigado_AltiumLib") (part "TP_R"))
    )
    (comp (ref "TP125")
      (value "TP")
      (footprint "TP10R")
      (description "Testpoint, Round 1.0mm Dia")
      (fields
        (field (name "PART NUMBER") "TP10R")
        (field (name "ADDED BY") "Jeremy D")
        (field (name "CHECKED BY") "Paul B")
      )
      (libsource (lib "LEGACY_Rigado_AltiumLib") (part "TP_R"))
    )
    (comp (ref "TP126")
      (value "TP")
      (footprint "TP10R")
      (description "Testpoint, Round 1.0mm Dia")
      (fields
        (field (name "PART NUMBER") "TP10R")
        (field (name "ADDED BY") "Jeremy D")
        (field (name "CHECKED BY") "Paul B")
      )
      (libsource (lib "LEGACY_Rigado_AltiumLib") (part "TP_R"))
    )
    (comp (ref "U2")
      (value "NCP691MN33T2G")
      (footprint "DFN-PSON.1P3X3-7pin_HS-7N")
      (description "LOW DROPOUT REGULATOR ON SEMICONDUCTOR NCP691MN33T2G 6DFN 3.3V 6V 1A")
      (fields
        (field (name "PART NUMBER") "UBXH12-0000459")
        (field (name "MANUFACTURER") "ON Semiconductor")
        (field (name "EDITOR") "hakan.ekfors")
        (field (name "RELEASED BY") "markus.wejrot")
      )
      (libsource (lib "UBX_Parts_DB_Lib") (part "NCP692MN33T2G"))
    )
    (comp (ref "U3")
      (value "TPS62131")
      (footprint "SamacSys:QFN50P300X300X100-17N-D")
      (description "Integrated Circuit")
      (fields
        (field (name "MANUFACTURER_PART_NUMBER") "TPS62130ARGTT")
        (field (name "MOUSER PART NUMBER") "595-TPS62130ARGTT")
      )
      (libsource (lib "*") (part "TPS62130ARGTT"))
    )
    (comp (ref "U4")
      (value "UBXH05-0000185")
      (footprint "QFN0.5P3x3-16Pin_W-Pad")
      (description "BQ24230 BATTERY CHARGER LI-ION USB 100-500MA 4.2V FLOAT VQFN-16 BQ24230RGTR")
      (fields
        (field (name "VOLTAGE") "5-6.5V")
        (field (name "MANUFACTURER") "Texas Instruments")
        (field (name "EDITOR") "eric.moog")
      )
      (libsource (lib "UBX_Parts_DB_Lib") (part "BQ24230RGTR"))
    )
  )
  (nets
    (net (code "1") (name "+3V3") (class "Default")
      (node (ref "C13") (pin "1") (pinfunction "1_1") (pintype "passive"))
      (node (ref "R30") (pin "2") (pinfunction "2_2") (pintype "passive"))
      (node (ref "R31") (pin "2") (pinfunction "2_2") (pintype "passive"))
      (node (ref "R37") (pin "1") (pinfunction "1_1") (pintype "passive"))
      (node (ref "U2") (pin "5") (pinfunction "OUT_5") (pintype "power_in"))
    )
    (net (code "2") (name "+5V") (class "Default")
      (node (ref "R148") (pin "2") (pinfunction "2_2") (pintype "passive"))
      (node (ref "SW1") (pin "4") (pinfunction "N.O-2_4") (pintype "passive"))
    )
    (net (code "3") (name "+Vin") (class "Default")
      (node (ref "D2") (pin "A") (pinfunction "Anode_A") (pintype "passive"))
    )
    (net (code "4") (name "/5V") (class "Default")
      (node (ref "C14") (pin "2") (pinfunction "2_2") (pintype "passive"))
      (node (ref "C20") (pin "2") (pinfunction "2_2") (pintype "passive"))
      (node (ref "D21") (pin "A") (pinfunction "Anode_A") (pintype "passive"))
      (node (ref "D3") (pin "A") (pinfunction "Anode_A") (pintype "passive"))
      (node (ref "D6") (pin "A") (pinfunction "Anode_A") (pintype "passive"))
      (node (ref "F1") (pin "2") (pinfunction "2_2") (pintype "passive"))
      (node (ref "F2") (pin "2") (pinfunction "2_2") (pintype "passive"))
    )
    (net (code "5") (name "/C9{slash}IO13{slash}USB_p") (class "Default")
      (node (ref "D4") (pin "2") (pinfunction "IO2_2") (pintype "passive"))
      (node (ref "J5") (pin "A6") (pinfunction "Dp1_A6") (pintype "power_in"))
      (node (ref "J5") (pin "B6") (pinfunction "Dp2_B6") (pintype "power_in"))
      (node (ref "TP3") (pin "1") (pintype "passive"))
    )
    (net (code "6") (name "/CHRG_N") (class "Default")
      (node (ref "D8") (pin "4") (pinfunction "K_RED_4") (pintype "passive"))
      (node (ref "U4") (pin "9") (pinfunction "CHRG_N_9") (pintype "open_collector"))
    )
    (net (code "7") (name "/D9{slash}IO12{slash}USB_n") (class "Default")
      (node (ref "D4") (pin "1") (pinfunction "IO1_1") (pintype "passive"))
      (node (ref "J5") (pin "A7") (pinfunction "Dn1_A7") (pintype "power_in"))
      (node (ref "J5") (pin "B7") (pinfunction "Dn2_B7") (pintype "power_in"))
      (node (ref "TP2") (pin "1") (pintype "passive"))
    )
    (net (code "8") (name "/DC_ind") (class "Default")
      (node (ref "L3") (pin "1") (pinfunction "1_1") (pintype "passive"))
      (node (ref "U3") (pin "1") (pinfunction "SW_1_1") (pintype "passive"))
      (node (ref "U3") (pin "2") (pinfunction "SW_2_2") (pintype "passive"))
      (node (ref "U3") (pin "3") (pinfunction "SW_3_3") (pintype "passive"))
    )
    (net (code "9") (name "/SHLDC") (class "Default")
      (node (ref "C24") (pin "2") (pinfunction "2_2") (pintype "passive"))
      (node (ref "J6") (pin "SHLD") (pinfunction "SHLD_SHLD") (pintype "power_in"))
      (node (ref "R49") (pin "1") (pinfunction "1_1") (pintype "passive"))
    )
    (net (code "10") (name "/SHLDM") (class "Default")
      (node (ref "C15") (pin "2") (pinfunction "2_2") (pintype "passive"))
      (node (ref "J5") (pin "SHLD") (pinfunction "SHLD_SHLD") (pintype "power_in"))
      (node (ref "R40") (pin "1") (pinfunction "1_1") (pintype "passive"))
    )
    (net (code "11") (name "/USB_n") (class "Default")
      (node (ref "D7") (pin "1") (pinfunction "IO1_1") (pintype "passive"))
      (node (ref "J6") (pin "A7") (pinfunction "Dn1_A7") (pintype "power_in"))
      (node (ref "J6") (pin "B7") (pinfunction "Dn2_B7") (pintype "power_in"))
      (node (ref "TP4") (pin "1") (pintype "passive"))
    )
    (net (code "12") (name "/USB_p") (class "Default")
      (node (ref "D7") (pin "2") (pinfunction "IO2_2") (pintype "passive"))
      (node (ref "J6") (pin "A6") (pinfunction "Dp1_A6") (pintype "power_in"))
      (node (ref "J6") (pin "B6") (pinfunction "Dp2_B6") (pintype "power_in"))
      (node (ref "TP5") (pin "1") (pintype "passive"))
    )
    (net (code "13") (name "BAT_IN") (class "Default")
      (node (ref "C25") (pin "2") (pinfunction "2_2") (pintype "passive"))
      (node (ref "C26") (pin "1") (pinfunction "1_1") (pintype "passive"))
      (node (ref "C27") (pin "2") (pinfunction "2_2") (pintype "passive"))
      (node (ref "F3") (pin "1") (pinfunction "1_1") (pintype "passive"))
      (node (ref "R26") (pin "2") (pinfunction "2_2") (pintype "passive"))
      (node (ref "R50") (pin "2") (pinfunction "2_2") (pintype "passive"))
      (node (ref "TP8") (pin "1") (pintype "passive"))
    )
    (net (code "14") (name "CHRG_OUT") (class "Default")
      (node (ref "C22") (pin "1") (pinfunction "1_1") (pintype "passive"))
      (node (ref "C23") (pin "1") (pinfunction "1_1") (pintype "passive"))
      (node (ref "R45") (pin "1") (pinfunction "1_1") (pintype "passive"))
      (node (ref "R48") (pin "2") (pinfunction "2_2") (pintype "passive"))
      (node (ref "R55") (pin "2") (pinfunction "2_2") (pintype "passive"))
      (node (ref "R56") (pin "2") (pinfunction "2_2") (pintype "passive"))
      (node (ref "TP6") (pin "1") (pintype "passive"))
      (node (ref "U4") (pin "10") (pinfunction "OUT_10") (pintype "output"))
      (node (ref "U4") (pin "11") (pinfunction "OUT_11") (pintype "output"))
    )
    (net (code "15") (name "GND") (class "Default")
      (node (ref "C12") (pin "2") (pinfunction "2_2") (pintype "passive"))
      (node (ref "C13") (pin "2") (pinfunction "2_2") (pintype "passive"))
      (node (ref "C14") (pin "1") (pinfunction "1_1") (pintype "passive"))
      (node (ref "C15") (pin "1") (pinfunction "1_1") (pintype "passive"))
      (node (ref "C16") (pin "2") (pinfunction "2_2") (pintype "passive"))
      (node (ref "C17") (pin "2") (pinfunction "2_2") (pintype "passive"))
      (node (ref "C18") (pin "2") (pinfunction "2_2") (pintype "passive"))
      (node (ref "C19") (pin "1") (pinfunction "1_1") (pintype "passive"))
      (node (ref "C20") (pin "1") (pinfunction "1_1") (pintype "passive"))
      (node (ref "C21") (pin "2") (pinfunction "2_2") (pintype "passive"))
      (node (ref "C22") (pin "2") (pinfunction "2_2") (pintype "passive"))
      (node (ref "C23") (pin "2") (pinfunction "2_2") (pintype "passive"))
      (node (ref "C24") (pin "1") (pinfunction "1_1") (pintype "passive"))
      (node (ref "C25") (pin "1") (pinfunction "1_1") (pintype "passive"))
      (node (ref "C26") (pin "2") (pinfunction "2_2") (pintype "passive"))
      (node (ref "C27") (pin "1") (pinfunction "1_1") (pintype "passive"))
      (node (ref "C28") (pin "2") (pinfunction "2_2") (pintype "passive"))
      (node (ref "C55") (pin "2") (pinfunction "2_2") (pintype "passive"))
      (node (ref "C56") (pin "2") (pinfunction "2_2") (pintype "passive"))
      (node (ref "D4") (pin "3") (pinfunction "GND_3") (pintype "power_in"))
      (node (ref "D5") (pin "2") (pinfunction "GND_2") (pintype "power_in"))
      (node (ref "D7") (pin "3") (pinfunction "GND_3") (pintype "power_in"))
      (node (ref "D8") (pin "3") (pinfunction "K_GREEN__3") (pintype "passive"))
      (node (ref "J5") (pin "A1B12") (pinfunction "GND_A1B12") (pintype "power_in"))
      (node (ref "J5") (pin "B1A12") (pinfunction "GND_B1A12") (pintype "power_in"))
      (node (ref "J6") (pin "A1B12") (pinfunction "GND_A1B12") (pintype "power_in"))
      (node (ref "J6") (pin "B1A12") (pinfunction "GND_B1A12") (pintype "power_in"))
      (node (ref "J7") (pin "1") (pinfunction "1_1") (pintype "passive"))
      (node (ref "J7") (pin "MH1") (pinfunction "MH1_MH1") (pintype "passive"))
      (node (ref "J8") (pin "2") (pinfunction "2_2") (pintype "passive"))
      (node (ref "R33") (pin "1") (pinfunction "1_1") (pintype "passive"))
      (node (ref "R34") (pin "1") (pinfunction "1_1") (pintype "passive"))
      (node (ref "R35") (pin "1") (pinfunction "1_1") (pintype "passive"))
      (node (ref "R38") (pin "1") (pinfunction "1_1") (pintype "passive"))
      (node (ref "R39") (pin "1") (pinfunction "1_1") (pintype "passive"))
      (node (ref "R40") (pin "2") (pinfunction "2_2") (pintype "passive"))
      (node (ref "R44") (pin "1") (pinfunction "1_1") (pintype "passive"))
      (node (ref "R46") (pin "1") (pinfunction "1_1") (pintype "passive"))
      (node (ref "R47") (pin "1") (pinfunction "1_1") (pintype "passive"))
      (node (ref "R49") (pin "2") (pinfunction "2_2") (pintype "passive"))
      (node (ref "R51") (pin "1") (pinfunction "1_1") (pintype "passive"))
      (node (ref "R52") (pin "1") (pinfunction "1_1") (pintype "passive"))
      (node (ref "R54") (pin "1") (pinfunction "1_1") (pintype "passive"))
      (node (ref "RT1") (pin "2") (pinfunction "2_2") (pintype "passive"))
      (node (ref "U2") (pin "2") (pinfunction "GND_2") (pintype "power_in"))
      (node (ref "U3") (pin "15") (pinfunction "PGND_1_15") (pintype "passive"))
      (node (ref "U3") (pin "16") (pinfunction "PGND_2_16") (pintype "passive"))
      (node (ref "U3") (pin "17") (pinfunction "EP_17") (pintype "passive"))
      (node (ref "U3") (pin "6") (pinfunction "AGND_6") (pintype "passive"))
      (node (ref "U3") (pin "7") (pinfunction "FSW_7") (pintype "passive"))
      (node (ref "U3") (pin "8") (pinfunction "DEF_8") (pintype "passive"))
      (node (ref "U4") (pin "15") (pinfunction "TD_15") (pintype "input"))
      (node (ref "U4") (pin "4") (pinfunction "CE_N_4") (pintype "input"))
      (node (ref "U4") (pin "5") (pinfunction "EN2_5") (pintype "input"))
      (node (ref "U4") (pin "8") (pinfunction "VSS_8") (pintype "power_in"))
      (node (ref "U4") (pin "EPAD") (pinfunction "EPAD_EPAD") (pintype "power_in"))
    )
    (net (code "16") (name "Net-(C12-Pad1)") (class "Default")
      (node (ref "C12") (pin "1") (pinfunction "1_1") (pintype "passive"))
      (node (ref "R29") (pin "2") (pinfunction "2_2") (pintype "passive"))
      (node (ref "R32") (pin "2") (pinfunction "2_2") (pintype "passive"))
      (node (ref "U2") (pin "1") (pinfunction "IN_1") (pintype "input"))
      (node (ref "U2") (pin "6") (pinfunction "IN_6") (pintype "input"))
    )
    (net (code "17") (name "Net-(C28-Pad1)") (class "Default")
      (node (ref "C28") (pin "1") (pinfunction "1_1") (pintype "passive"))
      (node (ref "R50") (pin "1") (pinfunction "1_1") (pintype "passive"))
      (node (ref "TP7") (pin "1") (pintype "passive"))
      (node (ref "U4") (pin "2") (pinfunction "BAT_2") (pintype "bidirectional"))
      (node (ref "U4") (pin "3") (pinfunction "BAT_3") (pintype "bidirectional"))
    )
    (net (code "18") (name "Net-(D4-Vcc)") (class "Default")
      (node (ref "D4") (pin "5") (pinfunction "Vcc_5") (pintype "power_in"))
      (node (ref "F1") (pin "1") (pinfunction "1_1") (pintype "passive"))
      (node (ref "J5") (pin "A4B9") (pinfunction "VBUS_A4B9") (pintype "power_in"))
      (node (ref "J5") (pin "B4A9") (pinfunction "VBUS_B4A9") (pintype "power_in"))
    )
    (net (code "19") (name "Net-(D7-Vcc)") (class "Default")
      (node (ref "D7") (pin "5") (pinfunction "Vcc_5") (pintype "power_in"))
      (node (ref "F2") (pin "1") (pinfunction "1_1") (pintype "passive"))
      (node (ref "J6") (pin "A4B9") (pinfunction "VBUS_A4B9") (pintype "power_in"))
      (node (ref "J6") (pin "B4A9") (pinfunction "VBUS_B4A9") (pintype "power_in"))
    )
    (net (code "20") (name "Net-(D8-A_1)") (class "Default")
      (node (ref "D8") (pin "1") (pinfunction "A_1_1") (pintype "passive"))
      (node (ref "R56") (pin "1") (pinfunction "1_1") (pintype "passive"))
    )
    (net (code "21") (name "Net-(D8-A_2)") (class "Default")
      (node (ref "D8") (pin "2") (pinfunction "A_2_2") (pintype "passive"))
      (node (ref "R55") (pin "1") (pinfunction "1_1") (pintype "passive"))
    )
    (net (code "22") (name "Net-(D21-Cathode)") (class "Default")
      (node (ref "D21") (pin "C") (pinfunction "Cathode_C") (pintype "passive"))
      (node (ref "SW1") (pin "5") (pinfunction "COM-2_5") (pintype "passive"))
    )
    (net (code "23") (name "Net-(F3-Pad2)") (class "Default")
      (node (ref "F3") (pin "2") (pinfunction "2_2") (pintype "passive"))
      (node (ref "J7") (pin "2") (pinfunction "2_2") (pintype "passive"))
      (node (ref "J8") (pin "1") (pinfunction "1_1") (pintype "passive"))
    )
    (net (code "24") (name "Net-(J5-CC1)") (class "Default")
      (node (ref "J5") (pin "A5") (pinfunction "CC1_A5") (pintype "power_in"))
      (node (ref "R39") (pin "2") (pinfunction "2_2") (pintype "passive"))
    )
    (net (code "25") (name "Net-(J5-CC2)") (class "Default")
      (node (ref "J5") (pin "B5") (pinfunction "CC2_B5") (pintype "power_in"))
      (node (ref "R38") (pin "2") (pinfunction "2_2") (pintype "passive"))
    )
    (net (code "26") (name "Net-(J6-CC1)") (class "Default")
      (node (ref "J6") (pin "A5") (pinfunction "CC1_A5") (pintype "power_in"))
      (node (ref "R47") (pin "2") (pinfunction "2_2") (pintype "passive"))
    )
    (net (code "27") (name "Net-(J6-CC2)") (class "Default")
      (node (ref "J6") (pin "B5") (pinfunction "CC2_B5") (pintype "power_in"))
      (node (ref "R46") (pin "2") (pinfunction "2_2") (pintype "passive"))
    )
    (net (code "28") (name "Net-(R53-Pad1)") (class "Default")
      (node (ref "R53") (pin "1") (pinfunction "1_1") (pintype "passive"))
      (node (ref "R54") (pin "2") (pinfunction "2_2") (pintype "passive"))
    )
    (net (code "29") (name "Net-(U2-ADJ)") (class "Default")
      (node (ref "R30") (pin "1") (pinfunction "1_1") (pintype "passive"))
      (node (ref "R31") (pin "1") (pinfunction "1_1") (pintype "passive"))
      (node (ref "R34") (pin "2") (pinfunction "2_2") (pintype "passive"))
      (node (ref "R35") (pin "2") (pinfunction "2_2") (pintype "passive"))
      (node (ref "U2") (pin "4") (pinfunction "ADJ_4") (pintype "input"))
    )
    (net (code "30") (name "Net-(U2-EN)") (class "Default")
      (node (ref "R32") (pin "1") (pinfunction "1_1") (pintype "passive"))
      (node (ref "R33") (pin "2") (pinfunction "2_2") (pintype "passive"))
      (node (ref "U2") (pin "3") (pinfunction "EN_3") (pintype "input"))
    )
    (net (code "31") (name "Net-(U3-AVIN)") (class "Default")
      (node (ref "C17") (pin "1") (pinfunction "1_1") (pintype "passive"))
      (node (ref "C18") (pin "1") (pinfunction "1_1") (pintype "passive"))
      (node (ref "R41") (pin "2") (pinfunction "2_2") (pintype "passive"))
      (node (ref "U3") (pin "10") (pinfunction "AVIN_10") (pintype "passive"))
      (node (ref "U3") (pin "11") (pinfunction "PVIN_1_11") (pintype "passive"))
      (node (ref "U3") (pin "12") (pinfunction "PVIN_2_12") (pintype "passive"))
      (node (ref "U3") (pin "13") (pinfunction "EN_13") (pintype "passive"))
    )
    (net (code "32") (name "Net-(U3-FB)") (class "Default")
      (node (ref "R43") (pin "1") (pinfunction "1_1") (pintype "passive"))
      (node (ref "R44") (pin "2") (pinfunction "2_2") (pintype "passive"))
      (node (ref "U3") (pin "5") (pinfunction "FB_5") (pintype "passive"))
    )
    (net (code "33") (name "Net-(U3-PG)") (class "Default")
      (node (ref "R42") (pin "1") (pinfunction "1_1") (pintype "passive"))
      (node (ref "U3") (pin "4") (pinfunction "PG_4") (pintype "passive"))
    )
    (net (code "34") (name "Net-(U3-SS{slash}TR)") (class "Default")
      (node (ref "C19") (pin "2") (pinfunction "2_2") (pintype "passive"))
      (node (ref "U3") (pin "9") (pinfunction "SS/TR_9") (pintype "passive"))
    )
    (net (code "35") (name "Net-(U4-ISET)") (class "Default")
      (node (ref "R53") (pin "2") (pinfunction "2_2") (pintype "passive"))
      (node (ref "TP9") (pin "1") (pintype "passive"))
      (node (ref "U4") (pin "16") (pinfunction "ISET_16") (pintype "bidirectional"))
    )
    (net (code "36") (name "Net-(U4-PGOOD_N)") (class "Default")
      (node (ref "R48") (pin "1") (pinfunction "1_1") (pintype "passive"))
      (node (ref "U4") (pin "7") (pinfunction "PGOOD_N_7") (pintype "open_collector"))
    )
    (net (code "37") (name "Net-(U4-TMR)") (class "Default")
      (node (ref "R51") (pin "2") (pinfunction "2_2") (pintype "passive"))
      (node (ref "U4") (pin "14") (pinfunction "TMR_14") (pintype "input"))
    )
    (net (code "38") (name "Net-(U4-TS)") (class "Default")
      (node (ref "R52") (pin "2") (pinfunction "2_2") (pintype "passive"))
      (node (ref "RT1") (pin "1") (pinfunction "1_1") (pintype "passive"))
      (node (ref "U4") (pin "1") (pinfunction "TS_1") (pintype "input"))
    )
    (net (code "39") (name "VBUS") (class "Default")
      (node (ref "C21") (pin "1") (pinfunction "1_1") (pintype "passive"))
      (node (ref "C55") (pin "1") (pinfunction "1_1") (pintype "passive"))
      (node (ref "D2") (pin "C") (pinfunction "Cathode_C") (pintype "passive"))
      (node (ref "D3") (pin "C") (pinfunction "Cathode_C") (pintype "passive"))
      (node (ref "D5") (pin "5") (pinfunction "OUT_5") (pintype "power_in"))
      (node (ref "D6") (pin "C") (pinfunction "Cathode_C") (pintype "passive"))
      (node (ref "SW1") (pin "2") (pinfunction "COM-1_2") (pintype "passive"))
      (node (ref "U4") (pin "13") (pinfunction "IN_13") (pintype "input"))
      (node (ref "U4") (pin "6") (pinfunction "EN1_6") (pintype "input"))
    )
    (net (code "40") (name "VDD_IO") (class "Default")
      (node (ref "R36") (pin "2") (pinfunction "2_2") (pintype "passive"))
    )
    (net (code "41") (name "VDD_MOD") (class "Default")
      (node (ref "C16") (pin "1") (pinfunction "1_1") (pintype "passive"))
      (node (ref "L3") (pin "2") (pinfunction "2_2") (pintype "passive"))
      (node (ref "R36") (pin "1") (pinfunction "1_1") (pintype "passive"))
      (node (ref "R37") (pin "2") (pinfunction "2_2") (pintype "passive"))
      (node (ref "R42") (pin "2") (pinfunction "2_2") (pintype "passive"))
      (node (ref "R43") (pin "2") (pinfunction "2_2") (pintype "passive"))
      (node (ref "U3") (pin "14") (pinfunction "VOS_14") (pintype "passive"))
    )
    (net (code "42") (name "VOUT") (class "Default")
      (node (ref "R148") (pin "1") (pinfunction "1_1") (pintype "passive"))
      (node (ref "R29") (pin "1") (pinfunction "1_1") (pintype "passive"))
      (node (ref "R41") (pin "1") (pinfunction "1_1") (pintype "passive"))
      (node (ref "SW1") (pin "1") (pinfunction "N.O-1_1") (pintype "passive"))
    )
    (net (code "43") (name "V_BAT") (class "Default")
      (node (ref "C56") (pin "1") (pinfunction "1_1") (pintype "passive"))
      (node (ref "D5") (pin "1") (pinfunction "VDD_1") (pintype "power_in"))
      (node (ref "D5") (pin "3") (pinfunction "EN_3") (pintype "input"))
      (node (ref "R26") (pin "1") (pinfunction "1_1") (pintype "passive"))
      (node (ref "R45") (pin "2") (pinfunction "2_2") (pintype "passive"))
      (node (ref "TP1") (pin "1") (pintype "passive"))
    )
    (net (code "44") (name "unconnected-(D4-IO3-Pad4)") (class "Default")
      (node (ref "D4") (pin "4") (pinfunction "IO3_4") (pintype "passive+no_connect"))
    )
    (net (code "45") (name "unconnected-(D5-NC-Pad4)") (class "Default")
      (node (ref "D5") (pin "4") (pinfunction "NC_4") (pintype "passive+no_connect"))
    )
    (net (code "46") (name "unconnected-(D7-IO3-Pad4)") (class "Default")
      (node (ref "D7") (pin "4") (pinfunction "IO3_4") (pintype "passive+no_connect"))
    )
    (net (code "47") (name "unconnected-(J5-SBU1-PadA8)") (class "Default")
      (node (ref "J5") (pin "A8") (pinfunction "SBU1_A8") (pintype "power_in+no_connect"))
    )
    (net (code "48") (name "unconnected-(J5-SBU2-PadB8)") (class "Default")
      (node (ref "J5") (pin "B8") (pinfunction "SBU2_B8") (pintype "power_in+no_connect"))
    )
    (net (code "49") (name "unconnected-(J6-SBU1-PadA8)") (class "Default")
      (node (ref "J6") (pin "A8") (pinfunction "SBU1_A8") (pintype "power_in+no_connect"))
    )
    (net (code "50") (name "unconnected-(J6-SBU2-PadB8)") (class "Default")
      (node (ref "J6") (pin "B8") (pinfunction "SBU2_B8") (pintype "power_in+no_connect"))
    )
    (net (code "51") (name "unconnected-(SW1-N.C-1-Pad3)") (class "Default")
      (node (ref "SW1") (pin "3") (pinfunction "N.C-1_3") (pintype "passive+no_connect"))
    )
    (net (code "52") (name "unconnected-(SW1-N.C-2-Pad6)") (class "Default")
      (node (ref "SW1") (pin "6") (pinfunction "N.C-2_6") (pintype "passive+no_connect"))
    )
    (net (code "53") (name "unconnected-(TP125-Pad1)") (class "Default")
      (node (ref "TP125") (pin "1") (pintype "passive+no_connect"))
    )
    (net (code "54") (name "unconnected-(TP126-Pad1)") (class "Default")
      (node (ref "TP126") (pin "1") (pintype "passive+no_connect"))
    )
    (net (code "55") (name "unconnected-(U4-ILIM-Pad12)") (class "Default")
      (node (ref "U4") (pin "12") (pinfunction "ILIM_12") (pintype "input+no_connect"))
    )
  )
)
